# M214X.net
KiCad netlist of a schematic drawn in EAGLE
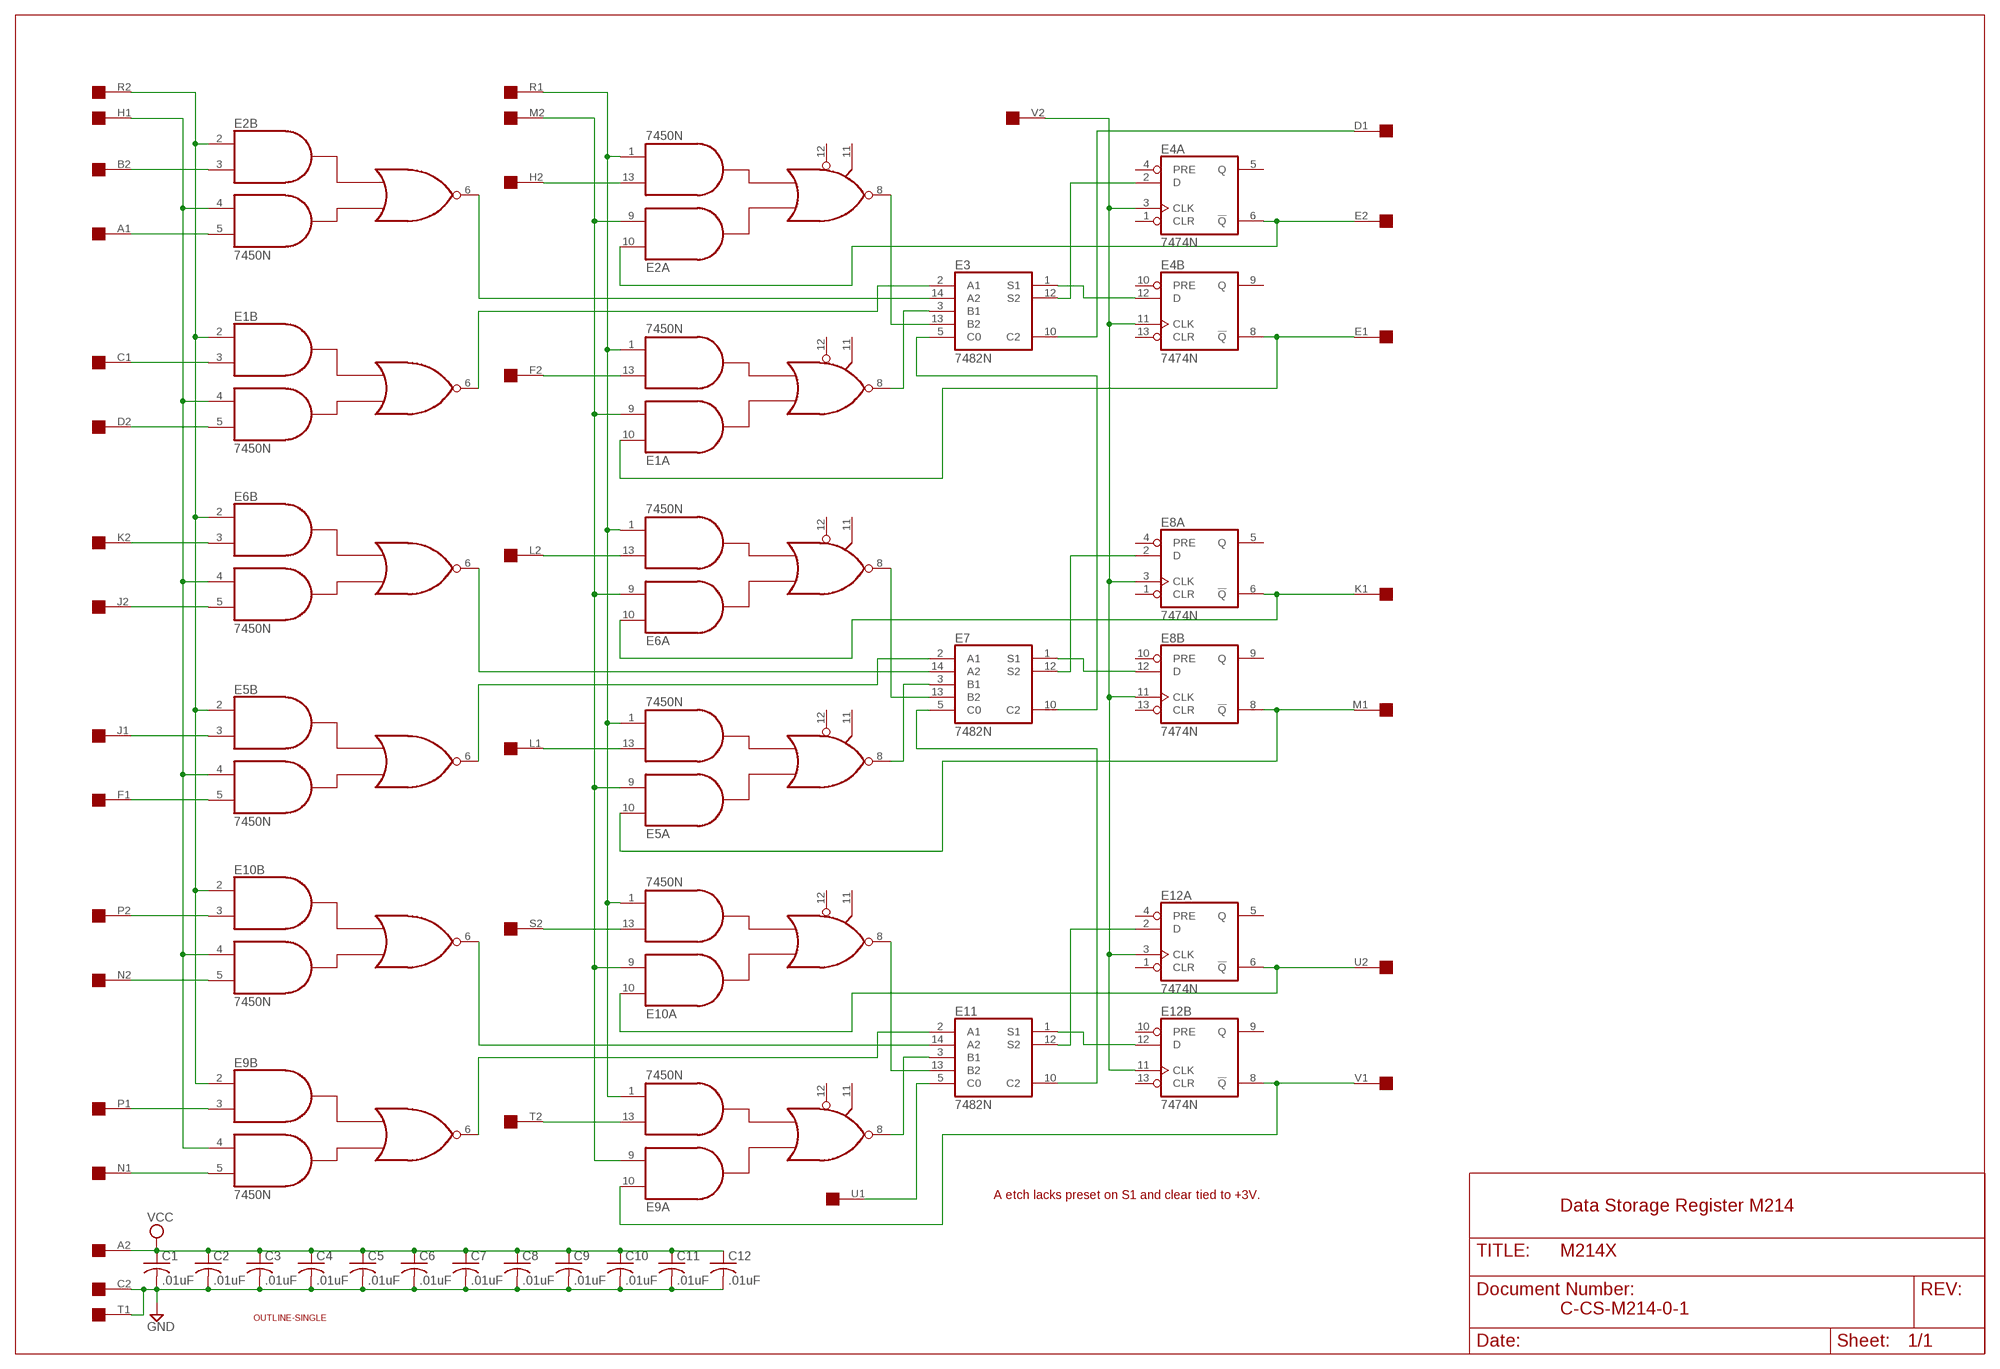
[diagram p0: schematic, sheet 1]

(export (version "E")
  (design (tool "Eeschema 10.0.6"))
  (components
    (comp (ref "C1")
      (value ".01uF")
      (footprint "eagle-import:C050-025X075")
      (libsource (lib "eagle-import") (part "C-US050-025X075"))
    )
    (comp (ref "C2")
      (value ".01uF")
      (footprint "eagle-import:C050-025X075")
      (libsource (lib "eagle-import") (part "C-US050-025X075"))
    )
    (comp (ref "C3")
      (value ".01uF")
      (footprint "eagle-import:C050-025X075")
      (libsource (lib "eagle-import") (part "C-US050-025X075"))
    )
    (comp (ref "C4")
      (value ".01uF")
      (footprint "eagle-import:C050-025X075")
      (libsource (lib "eagle-import") (part "C-US050-025X075"))
    )
    (comp (ref "C5")
      (value ".01uF")
      (footprint "eagle-import:C050-025X075")
      (libsource (lib "eagle-import") (part "C-US050-025X075"))
    )
    (comp (ref "C6")
      (value ".01uF")
      (footprint "eagle-import:C050-025X075")
      (libsource (lib "eagle-import") (part "C-US050-025X075"))
    )
    (comp (ref "C7")
      (value ".01uF")
      (footprint "eagle-import:C050-025X075")
      (libsource (lib "eagle-import") (part "C-US050-025X075"))
    )
    (comp (ref "C8")
      (value ".01uF")
      (footprint "eagle-import:C050-025X075")
      (libsource (lib "eagle-import") (part "C-US050-025X075"))
    )
    (comp (ref "C9")
      (value ".01uF")
      (footprint "eagle-import:C050-025X075")
      (libsource (lib "eagle-import") (part "C-US050-025X075"))
    )
    (comp (ref "C10")
      (value ".01uF")
      (footprint "eagle-import:C050-025X075")
      (libsource (lib "eagle-import") (part "C-US050-025X075"))
    )
    (comp (ref "C11")
      (value ".01uF")
      (footprint "eagle-import:C050-025X075")
      (libsource (lib "eagle-import") (part "C-US050-025X075"))
    )
    (comp (ref "C12")
      (value ".01uF")
      (footprint "eagle-import:C050-025X075")
      (libsource (lib "eagle-import") (part "C-US050-025X075"))
    )
    (comp (ref "E1")
      (value "7450N")
      (footprint "eagle-import:DIL14")
      (libsource (lib "eagle-import") (part "7450N"))
    )
    (comp (ref "E2")
      (value "7450N")
      (footprint "eagle-import:DIL14")
      (libsource (lib "eagle-import") (part "7450N"))
    )
    (comp (ref "E3")
      (value "7482N")
      (footprint "eagle-import:DIL14")
      (libsource (lib "eagle-import") (part "7482N"))
    )
    (comp (ref "E4")
      (value "7474N")
      (footprint "eagle-import:DIL14")
      (libsource (lib "eagle-import") (part "7474NS"))
    )
    (comp (ref "E5")
      (value "7450N")
      (footprint "eagle-import:DIL14")
      (libsource (lib "eagle-import") (part "7450N"))
    )
    (comp (ref "E6")
      (value "7450N")
      (footprint "eagle-import:DIL14")
      (libsource (lib "eagle-import") (part "7450N"))
    )
    (comp (ref "E7")
      (value "7482N")
      (footprint "eagle-import:DIL14")
      (libsource (lib "eagle-import") (part "7482N"))
    )
    (comp (ref "E8")
      (value "7474N")
      (footprint "eagle-import:DIL14")
      (libsource (lib "eagle-import") (part "7474NS"))
    )
    (comp (ref "E9")
      (value "7450N")
      (footprint "eagle-import:DIL14")
      (libsource (lib "eagle-import") (part "7450N"))
    )
    (comp (ref "E10")
      (value "7450N")
      (footprint "eagle-import:DIL14")
      (libsource (lib "eagle-import") (part "7450N"))
    )
    (comp (ref "E11")
      (value "7482N")
      (footprint "eagle-import:DIL14")
      (libsource (lib "eagle-import") (part "7482N"))
    )
    (comp (ref "E12")
      (value "7474N")
      (footprint "eagle-import:DIL14")
      (libsource (lib "eagle-import") (part "7474NS"))
    )
    (comp (ref "U$1")
      (value "OUTLINE-SINGLE")
      (footprint "eagle-import:SINGLE")
      (libsource (lib "eagle-import") (part "OUTLINE-SINGLE"))
    )
    (comp (ref "U$2")
      (value "SINGLE")
      (footprint "eagle-import:EDGE-CON2")
      (libsource (lib "eagle-import") (part "SINGLE"))
    )
  )
  (nets
    (net (code "1") (name "GND") (class "Default")
      (node (ref "C1") (pin "2") (pinfunction "2_2") (pintype "passive"))
      (node (ref "C10") (pin "2") (pinfunction "2_2") (pintype "passive"))
      (node (ref "C11") (pin "2") (pinfunction "2_2") (pintype "passive"))
      (node (ref "C12") (pin "2") (pinfunction "2_2") (pintype "passive"))
      (node (ref "C2") (pin "2") (pinfunction "2_2") (pintype "passive"))
      (node (ref "C3") (pin "2") (pinfunction "2_2") (pintype "passive"))
      (node (ref "C4") (pin "2") (pinfunction "2_2") (pintype "passive"))
      (node (ref "C5") (pin "2") (pinfunction "2_2") (pintype "passive"))
      (node (ref "C6") (pin "2") (pinfunction "2_2") (pintype "passive"))
      (node (ref "C7") (pin "2") (pinfunction "2_2") (pintype "passive"))
      (node (ref "C8") (pin "2") (pinfunction "2_2") (pintype "passive"))
      (node (ref "C9") (pin "2") (pinfunction "2_2") (pintype "passive"))
      (node (ref "U$2") (pin "C2") (pinfunction "1_C2") (pintype "bidirectional"))
      (node (ref "U$2") (pin "T1") (pinfunction "1_T1") (pintype "bidirectional"))
    )
    (net (code "2") (name "Net-(E1A-I1)") (class "Default")
      (node (ref "E1") (pin "10") (pinfunction "I1_10") (pintype "input"))
      (node (ref "E4") (pin "8") (pinfunction "~{Q}_8") (pintype "output"))
      (node (ref "U$2") (pin "E1") (pinfunction "1_E1") (pintype "bidirectional"))
    )
    (net (code "3") (name "Net-(E1A-I3)") (class "Default")
      (node (ref "E1") (pin "13") (pinfunction "I3_13") (pintype "input"))
      (node (ref "U$2") (pin "F2") (pinfunction "1_F2") (pintype "bidirectional"))
    )
    (net (code "4") (name "Net-(E1A-O)") (class "Default")
      (node (ref "E1") (pin "8") (pinfunction "O_8") (pintype "output"))
      (node (ref "E3") (pin "3") (pinfunction "B1_3") (pintype "input"))
    )
    (net (code "5") (name "Net-(E1B-I2)") (class "Default")
      (node (ref "E1") (pin "3") (pinfunction "I2_3") (pintype "input"))
      (node (ref "U$2") (pin "C1") (pinfunction "1_C1") (pintype "bidirectional"))
    )
    (net (code "6") (name "Net-(E1B-I4)") (class "Default")
      (node (ref "E1") (pin "5") (pinfunction "I4_5") (pintype "input"))
      (node (ref "U$2") (pin "D2") (pinfunction "1_D2") (pintype "bidirectional"))
    )
    (net (code "7") (name "Net-(E1B-O)") (class "Default")
      (node (ref "E1") (pin "6") (pinfunction "O_6") (pintype "output"))
      (node (ref "E3") (pin "2") (pinfunction "A1_2") (pintype "input"))
    )
    (net (code "8") (name "Net-(E2A-I1)") (class "Default")
      (node (ref "E2") (pin "10") (pinfunction "I1_10") (pintype "input"))
      (node (ref "E4") (pin "6") (pinfunction "~{Q}_6") (pintype "output"))
      (node (ref "U$2") (pin "E2") (pinfunction "1_E2") (pintype "bidirectional"))
    )
    (net (code "9") (name "Net-(E2A-I3)") (class "Default")
      (node (ref "E2") (pin "13") (pinfunction "I3_13") (pintype "input"))
      (node (ref "U$2") (pin "H2") (pinfunction "1_H2") (pintype "bidirectional"))
    )
    (net (code "10") (name "Net-(E2A-O)") (class "Default")
      (node (ref "E2") (pin "8") (pinfunction "O_8") (pintype "output"))
      (node (ref "E3") (pin "13") (pinfunction "B2_13") (pintype "input"))
    )
    (net (code "11") (name "Net-(E2B-I2)") (class "Default")
      (node (ref "E2") (pin "3") (pinfunction "I2_3") (pintype "input"))
      (node (ref "U$2") (pin "B2") (pinfunction "1_B2") (pintype "bidirectional"))
    )
    (net (code "12") (name "Net-(E2B-I4)") (class "Default")
      (node (ref "E2") (pin "5") (pinfunction "I4_5") (pintype "input"))
      (node (ref "U$2") (pin "A1") (pinfunction "1_A1") (pintype "bidirectional"))
    )
    (net (code "13") (name "Net-(E2B-O)") (class "Default")
      (node (ref "E2") (pin "6") (pinfunction "O_6") (pintype "output"))
      (node (ref "E3") (pin "14") (pinfunction "A2_14") (pintype "input"))
    )
    (net (code "14") (name "Net-(E3E-C0)") (class "Default")
      (node (ref "E3") (pin "5") (pinfunction "C0_5") (pintype "input"))
      (node (ref "E7") (pin "10") (pinfunction "C2_10") (pintype "output"))
    )
    (net (code "15") (name "Net-(E3E-C2)") (class "Default")
      (node (ref "E3") (pin "10") (pinfunction "C2_10") (pintype "output"))
      (node (ref "U$2") (pin "D1") (pinfunction "1_D1") (pintype "bidirectional"))
    )
    (net (code "16") (name "Net-(E3E-S1)") (class "Default")
      (node (ref "E3") (pin "1") (pinfunction "S1_1") (pintype "output"))
      (node (ref "E4") (pin "12") (pinfunction "D_12") (pintype "input"))
    )
    (net (code "17") (name "Net-(E3E-S2)") (class "Default")
      (node (ref "E3") (pin "12") (pinfunction "S2_12") (pintype "output"))
      (node (ref "E4") (pin "2") (pinfunction "D_2") (pintype "input"))
    )
    (net (code "18") (name "Net-(E5A-I1)") (class "Default")
      (node (ref "E5") (pin "10") (pinfunction "I1_10") (pintype "input"))
      (node (ref "E8") (pin "8") (pinfunction "~{Q}_8") (pintype "output"))
      (node (ref "U$2") (pin "M1") (pinfunction "1_M1") (pintype "bidirectional"))
    )
    (net (code "19") (name "Net-(E5A-I3)") (class "Default")
      (node (ref "E5") (pin "13") (pinfunction "I3_13") (pintype "input"))
      (node (ref "U$2") (pin "L1") (pinfunction "1_L1") (pintype "bidirectional"))
    )
    (net (code "20") (name "Net-(E5A-O)") (class "Default")
      (node (ref "E5") (pin "8") (pinfunction "O_8") (pintype "output"))
      (node (ref "E7") (pin "3") (pinfunction "B1_3") (pintype "input"))
    )
    (net (code "21") (name "Net-(E5B-I2)") (class "Default")
      (node (ref "E5") (pin "3") (pinfunction "I2_3") (pintype "input"))
      (node (ref "U$2") (pin "J1") (pinfunction "1_J1") (pintype "bidirectional"))
    )
    (net (code "22") (name "Net-(E5B-I4)") (class "Default")
      (node (ref "E5") (pin "5") (pinfunction "I4_5") (pintype "input"))
      (node (ref "U$2") (pin "F1") (pinfunction "1_F1") (pintype "bidirectional"))
    )
    (net (code "23") (name "Net-(E5B-O)") (class "Default")
      (node (ref "E5") (pin "6") (pinfunction "O_6") (pintype "output"))
      (node (ref "E7") (pin "2") (pinfunction "A1_2") (pintype "input"))
    )
    (net (code "24") (name "Net-(E6A-I1)") (class "Default")
      (node (ref "E6") (pin "10") (pinfunction "I1_10") (pintype "input"))
      (node (ref "E8") (pin "6") (pinfunction "~{Q}_6") (pintype "output"))
      (node (ref "U$2") (pin "K1") (pinfunction "1_K1") (pintype "bidirectional"))
    )
    (net (code "25") (name "Net-(E6A-I3)") (class "Default")
      (node (ref "E6") (pin "13") (pinfunction "I3_13") (pintype "input"))
      (node (ref "U$2") (pin "L2") (pinfunction "1_L2") (pintype "bidirectional"))
    )
    (net (code "26") (name "Net-(E6A-O)") (class "Default")
      (node (ref "E6") (pin "8") (pinfunction "O_8") (pintype "output"))
      (node (ref "E7") (pin "13") (pinfunction "B2_13") (pintype "input"))
    )
    (net (code "27") (name "Net-(E6B-I2)") (class "Default")
      (node (ref "E6") (pin "3") (pinfunction "I2_3") (pintype "input"))
      (node (ref "U$2") (pin "K2") (pinfunction "1_K2") (pintype "bidirectional"))
    )
    (net (code "28") (name "Net-(E6B-I4)") (class "Default")
      (node (ref "E6") (pin "5") (pinfunction "I4_5") (pintype "input"))
      (node (ref "U$2") (pin "J2") (pinfunction "1_J2") (pintype "bidirectional"))
    )
    (net (code "29") (name "Net-(E6B-O)") (class "Default")
      (node (ref "E6") (pin "6") (pinfunction "O_6") (pintype "output"))
      (node (ref "E7") (pin "14") (pinfunction "A2_14") (pintype "input"))
    )
    (net (code "30") (name "Net-(E7E-S1)") (class "Default")
      (node (ref "E7") (pin "1") (pinfunction "S1_1") (pintype "output"))
      (node (ref "E8") (pin "12") (pinfunction "D_12") (pintype "input"))
    )
    (net (code "31") (name "Net-(E7E-S2)") (class "Default")
      (node (ref "E7") (pin "12") (pinfunction "S2_12") (pintype "output"))
      (node (ref "E8") (pin "2") (pinfunction "D_2") (pintype "input"))
    )
    (net (code "32") (name "Net-(E9A-I3)") (class "Default")
      (node (ref "E9") (pin "13") (pinfunction "I3_13") (pintype "input"))
      (node (ref "U$2") (pin "T2") (pinfunction "1_T2") (pintype "bidirectional"))
    )
    (net (code "33") (name "Net-(E9B-I2)") (class "Default")
      (node (ref "E9") (pin "3") (pinfunction "I2_3") (pintype "input"))
      (node (ref "U$2") (pin "P1") (pinfunction "1_P1") (pintype "bidirectional"))
    )
    (net (code "34") (name "Net-(E9B-I4)") (class "Default")
      (node (ref "E9") (pin "5") (pinfunction "I4_5") (pintype "input"))
      (node (ref "U$2") (pin "N1") (pinfunction "1_N1") (pintype "bidirectional"))
    )
    (net (code "35") (name "Net-(E10A-I1)") (class "Default")
      (node (ref "E10") (pin "10") (pinfunction "I1_10") (pintype "input"))
      (node (ref "E12") (pin "6") (pinfunction "~{Q}_6") (pintype "output"))
      (node (ref "U$2") (pin "U2") (pinfunction "1_U2") (pintype "bidirectional"))
    )
    (net (code "36") (name "Net-(E10A-I2)") (class "Default")
      (node (ref "E1") (pin "9") (pinfunction "I2_9") (pintype "input"))
      (node (ref "E10") (pin "9") (pinfunction "I2_9") (pintype "input"))
      (node (ref "E2") (pin "9") (pinfunction "I2_9") (pintype "input"))
      (node (ref "E5") (pin "9") (pinfunction "I2_9") (pintype "input"))
      (node (ref "E6") (pin "9") (pinfunction "I2_9") (pintype "input"))
      (node (ref "E9") (pin "9") (pinfunction "I2_9") (pintype "input"))
      (node (ref "U$2") (pin "M2") (pinfunction "1_M2") (pintype "bidirectional"))
    )
    (net (code "37") (name "Net-(E10A-I3)") (class "Default")
      (node (ref "E10") (pin "13") (pinfunction "I3_13") (pintype "input"))
      (node (ref "U$2") (pin "S2") (pinfunction "1_S2") (pintype "bidirectional"))
    )
    (net (code "38") (name "Net-(E10A-I4)") (class "Default")
      (node (ref "E1") (pin "1") (pinfunction "I4_1") (pintype "input"))
      (node (ref "E10") (pin "1") (pinfunction "I4_1") (pintype "input"))
      (node (ref "E2") (pin "1") (pinfunction "I4_1") (pintype "input"))
      (node (ref "E5") (pin "1") (pinfunction "I4_1") (pintype "input"))
      (node (ref "E6") (pin "1") (pinfunction "I4_1") (pintype "input"))
      (node (ref "E9") (pin "1") (pinfunction "I4_1") (pintype "input"))
      (node (ref "U$2") (pin "R1") (pinfunction "1_R1") (pintype "bidirectional"))
    )
    (net (code "39") (name "Net-(E10A-O)") (class "Default")
      (node (ref "E10") (pin "8") (pinfunction "O_8") (pintype "output"))
      (node (ref "E11") (pin "13") (pinfunction "B2_13") (pintype "input"))
    )
    (net (code "40") (name "Net-(E10B-I1)") (class "Default")
      (node (ref "E1") (pin "2") (pinfunction "I1_2") (pintype "input"))
      (node (ref "E10") (pin "2") (pinfunction "I1_2") (pintype "input"))
      (node (ref "E2") (pin "2") (pinfunction "I1_2") (pintype "input"))
      (node (ref "E5") (pin "2") (pinfunction "I1_2") (pintype "input"))
      (node (ref "E6") (pin "2") (pinfunction "I1_2") (pintype "input"))
      (node (ref "E9") (pin "2") (pinfunction "I1_2") (pintype "input"))
      (node (ref "U$2") (pin "R2") (pinfunction "1_R2") (pintype "bidirectional"))
    )
    (net (code "41") (name "Net-(E10B-I2)") (class "Default")
      (node (ref "E10") (pin "3") (pinfunction "I2_3") (pintype "input"))
      (node (ref "U$2") (pin "P2") (pinfunction "1_P2") (pintype "bidirectional"))
    )
    (net (code "42") (name "Net-(E10B-I3)") (class "Default")
      (node (ref "E1") (pin "4") (pinfunction "I3_4") (pintype "input"))
      (node (ref "E10") (pin "4") (pinfunction "I3_4") (pintype "input"))
      (node (ref "E2") (pin "4") (pinfunction "I3_4") (pintype "input"))
      (node (ref "E5") (pin "4") (pinfunction "I3_4") (pintype "input"))
      (node (ref "E6") (pin "4") (pinfunction "I3_4") (pintype "input"))
      (node (ref "E9") (pin "4") (pinfunction "I3_4") (pintype "input"))
      (node (ref "U$2") (pin "H1") (pinfunction "1_H1") (pintype "bidirectional"))
    )
    (net (code "43") (name "Net-(E10B-I4)") (class "Default")
      (node (ref "E10") (pin "5") (pinfunction "I4_5") (pintype "input"))
      (node (ref "U$2") (pin "N2") (pinfunction "1_N2") (pintype "bidirectional"))
    )
    (net (code "44") (name "Net-(E10B-O)") (class "Default")
      (node (ref "E10") (pin "6") (pinfunction "O_6") (pintype "output"))
      (node (ref "E11") (pin "14") (pinfunction "A2_14") (pintype "input"))
    )
    (net (code "45") (name "Net-(E11E-A1)") (class "Default")
      (node (ref "E11") (pin "2") (pinfunction "A1_2") (pintype "input"))
      (node (ref "E9") (pin "6") (pinfunction "O_6") (pintype "output"))
    )
    (net (code "46") (name "Net-(E11E-B1)") (class "Default")
      (node (ref "E11") (pin "3") (pinfunction "B1_3") (pintype "input"))
      (node (ref "E9") (pin "8") (pinfunction "O_8") (pintype "output"))
    )
    (net (code "47") (name "Net-(E11E-C0)") (class "Default")
      (node (ref "E11") (pin "5") (pinfunction "C0_5") (pintype "input"))
      (node (ref "U$2") (pin "U1") (pinfunction "1_U1") (pintype "bidirectional"))
    )
    (net (code "48") (name "Net-(E11E-C2)") (class "Default")
      (node (ref "E11") (pin "10") (pinfunction "C2_10") (pintype "output"))
      (node (ref "E7") (pin "5") (pinfunction "C0_5") (pintype "input"))
    )
    (net (code "49") (name "Net-(E11E-S1)") (class "Default")
      (node (ref "E11") (pin "1") (pinfunction "S1_1") (pintype "output"))
      (node (ref "E12") (pin "12") (pinfunction "D_12") (pintype "input"))
    )
    (net (code "50") (name "Net-(E11E-S2)") (class "Default")
      (node (ref "E11") (pin "12") (pinfunction "S2_12") (pintype "output"))
      (node (ref "E12") (pin "2") (pinfunction "D_2") (pintype "input"))
    )
    (net (code "51") (name "Net-(E12A-CLK)") (class "Default")
      (node (ref "E12") (pin "11") (pinfunction "CLK_11") (pintype "input"))
      (node (ref "E12") (pin "3") (pinfunction "CLK_3") (pintype "input"))
      (node (ref "E4") (pin "11") (pinfunction "CLK_11") (pintype "input"))
      (node (ref "E4") (pin "3") (pinfunction "CLK_3") (pintype "input"))
      (node (ref "E8") (pin "11") (pinfunction "CLK_11") (pintype "input"))
      (node (ref "E8") (pin "3") (pinfunction "CLK_3") (pintype "input"))
      (node (ref "U$2") (pin "V2") (pinfunction "1_V2") (pintype "bidirectional"))
    )
    (net (code "52") (name "Net-(E12B-~{Q})") (class "Default")
      (node (ref "E12") (pin "8") (pinfunction "~{Q}_8") (pintype "output"))
      (node (ref "E9") (pin "10") (pinfunction "I1_10") (pintype "input"))
      (node (ref "U$2") (pin "V1") (pinfunction "1_V1") (pintype "bidirectional"))
    )
    (net (code "53") (name "VCC") (class "Default")
      (node (ref "C1") (pin "1") (pinfunction "1_1") (pintype "passive"))
      (node (ref "C10") (pin "1") (pinfunction "1_1") (pintype "passive"))
      (node (ref "C11") (pin "1") (pinfunction "1_1") (pintype "passive"))
      (node (ref "C12") (pin "1") (pinfunction "1_1") (pintype "passive"))
      (node (ref "C2") (pin "1") (pinfunction "1_1") (pintype "passive"))
      (node (ref "C3") (pin "1") (pinfunction "1_1") (pintype "passive"))
      (node (ref "C4") (pin "1") (pinfunction "1_1") (pintype "passive"))
      (node (ref "C5") (pin "1") (pinfunction "1_1") (pintype "passive"))
      (node (ref "C6") (pin "1") (pinfunction "1_1") (pintype "passive"))
      (node (ref "C7") (pin "1") (pinfunction "1_1") (pintype "passive"))
      (node (ref "C8") (pin "1") (pinfunction "1_1") (pintype "passive"))
      (node (ref "C9") (pin "1") (pinfunction "1_1") (pintype "passive"))
      (node (ref "U$2") (pin "A2") (pinfunction "1_A2") (pintype "bidirectional"))
    )
    (net (code "54") (name "unconnected-(E1A-I5-Pad12)") (class "Default")
      (node (ref "E1") (pin "12") (pinfunction "I5_12") (pintype "passive"))
    )
    (net (code "55") (name "unconnected-(E1A-I6-Pad11)") (class "Default")
      (node (ref "E1") (pin "11") (pinfunction "I6_11") (pintype "passive"))
    )
    (net (code "56") (name "unconnected-(E2A-I5-Pad12)") (class "Default")
      (node (ref "E2") (pin "12") (pinfunction "I5_12") (pintype "passive"))
    )
    (net (code "57") (name "unconnected-(E2A-I6-Pad11)") (class "Default")
      (node (ref "E2") (pin "11") (pinfunction "I6_11") (pintype "passive"))
    )
    (net (code "58") (name "unconnected-(E4A-CLR-Pad1)") (class "Default")
      (node (ref "E4") (pin "1") (pinfunction "CLR_1") (pintype "input"))
    )
    (net (code "59") (name "unconnected-(E4A-PRE-Pad4)") (class "Default")
      (node (ref "E4") (pin "4") (pinfunction "PRE_4") (pintype "input"))
    )
    (net (code "60") (name "unconnected-(E4A-Q-Pad5)") (class "Default")
      (node (ref "E4") (pin "5") (pinfunction "Q_5") (pintype "output"))
    )
    (net (code "61") (name "unconnected-(E4B-CLR-Pad13)") (class "Default")
      (node (ref "E4") (pin "13") (pinfunction "CLR_13") (pintype "input"))
    )
    (net (code "62") (name "unconnected-(E4B-PRE-Pad10)") (class "Default")
      (node (ref "E4") (pin "10") (pinfunction "PRE_10") (pintype "input"))
    )
    (net (code "63") (name "unconnected-(E4B-Q-Pad9)") (class "Default")
      (node (ref "E4") (pin "9") (pinfunction "Q_9") (pintype "output"))
    )
    (net (code "64") (name "unconnected-(E5A-I5-Pad12)") (class "Default")
      (node (ref "E5") (pin "12") (pinfunction "I5_12") (pintype "passive"))
    )
    (net (code "65") (name "unconnected-(E5A-I6-Pad11)") (class "Default")
      (node (ref "E5") (pin "11") (pinfunction "I6_11") (pintype "passive"))
    )
    (net (code "66") (name "unconnected-(E6A-I5-Pad12)") (class "Default")
      (node (ref "E6") (pin "12") (pinfunction "I5_12") (pintype "passive"))
    )
    (net (code "67") (name "unconnected-(E6A-I6-Pad11)") (class "Default")
      (node (ref "E6") (pin "11") (pinfunction "I6_11") (pintype "passive"))
    )
    (net (code "68") (name "unconnected-(E8A-CLR-Pad1)") (class "Default")
      (node (ref "E8") (pin "1") (pinfunction "CLR_1") (pintype "input"))
    )
    (net (code "69") (name "unconnected-(E8A-PRE-Pad4)") (class "Default")
      (node (ref "E8") (pin "4") (pinfunction "PRE_4") (pintype "input"))
    )
    (net (code "70") (name "unconnected-(E8A-Q-Pad5)") (class "Default")
      (node (ref "E8") (pin "5") (pinfunction "Q_5") (pintype "output"))
    )
    (net (code "71") (name "unconnected-(E8B-CLR-Pad13)") (class "Default")
      (node (ref "E8") (pin "13") (pinfunction "CLR_13") (pintype "input"))
    )
    (net (code "72") (name "unconnected-(E8B-PRE-Pad10)") (class "Default")
      (node (ref "E8") (pin "10") (pinfunction "PRE_10") (pintype "input"))
    )
    (net (code "73") (name "unconnected-(E8B-Q-Pad9)") (class "Default")
      (node (ref "E8") (pin "9") (pinfunction "Q_9") (pintype "output"))
    )
    (net (code "74") (name "unconnected-(E9A-I5-Pad12)") (class "Default")
      (node (ref "E9") (pin "12") (pinfunction "I5_12") (pintype "passive"))
    )
    (net (code "75") (name "unconnected-(E9A-I6-Pad11)") (class "Default")
      (node (ref "E9") (pin "11") (pinfunction "I6_11") (pintype "passive"))
    )
    (net (code "76") (name "unconnected-(E10A-I5-Pad12)") (class "Default")
      (node (ref "E10") (pin "12") (pinfunction "I5_12") (pintype "passive"))
    )
    (net (code "77") (name "unconnected-(E10A-I6-Pad11)") (class "Default")
      (node (ref "E10") (pin "11") (pinfunction "I6_11") (pintype "passive"))
    )
    (net (code "78") (name "unconnected-(E12A-CLR-Pad1)") (class "Default")
      (node (ref "E12") (pin "1") (pinfunction "CLR_1") (pintype "input"))
    )
    (net (code "79") (name "unconnected-(E12A-PRE-Pad4)") (class "Default")
      (node (ref "E12") (pin "4") (pinfunction "PRE_4") (pintype "input"))
    )
    (net (code "80") (name "unconnected-(E12A-Q-Pad5)") (class "Default")
      (node (ref "E12") (pin "5") (pinfunction "Q_5") (pintype "output"))
    )
    (net (code "81") (name "unconnected-(E12B-CLR-Pad13)") (class "Default")
      (node (ref "E12") (pin "13") (pinfunction "CLR_13") (pintype "input"))
    )
    (net (code "82") (name "unconnected-(E12B-PRE-Pad10)") (class "Default")
      (node (ref "E12") (pin "10") (pinfunction "PRE_10") (pintype "input"))
    )
    (net (code "83") (name "unconnected-(E12B-Q-Pad9)") (class "Default")
      (node (ref "E12") (pin "9") (pinfunction "Q_9") (pintype "output"))
    )
  )
)
